# Wetter.net
KiCad netlist of a schematic drawn in EAGLE
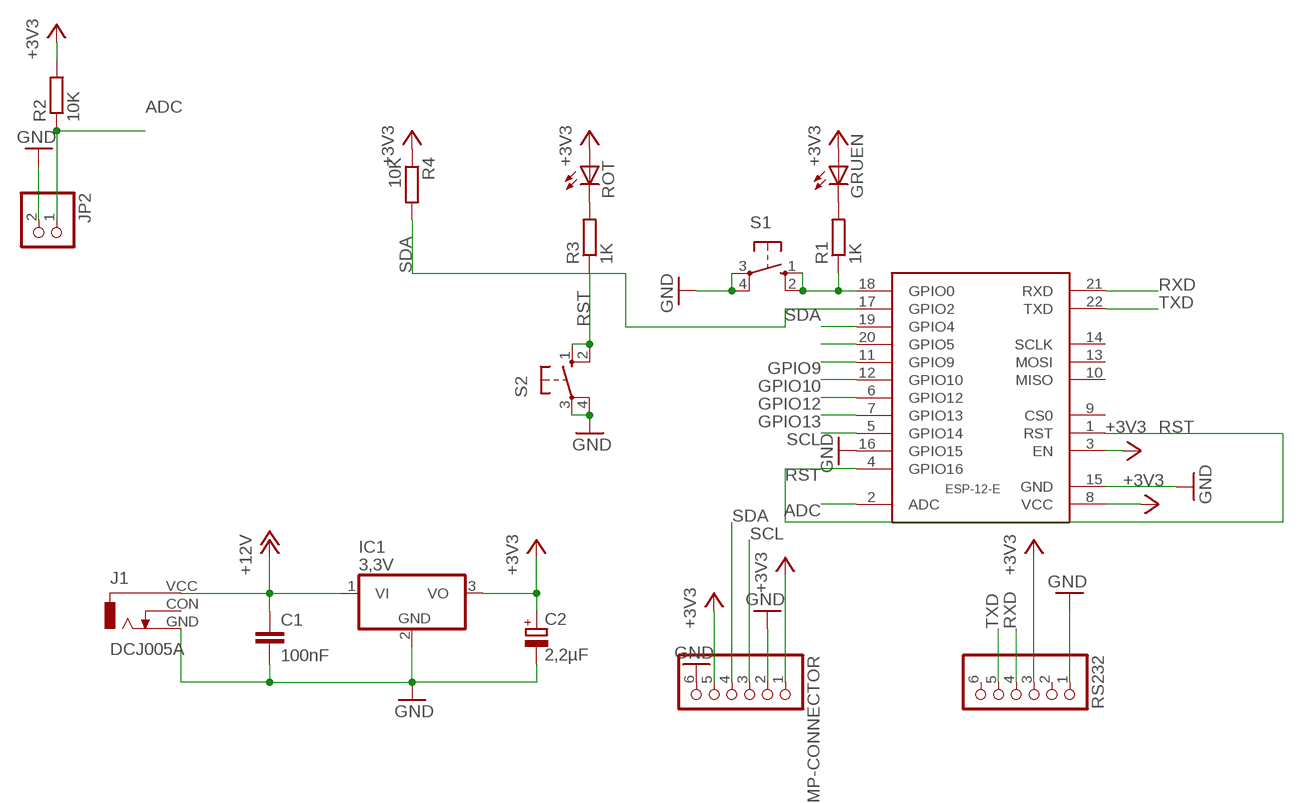
[diagram p0: schematic, sheet 1]

(export (version "E")
  (design (tool "Eeschema 10.0.6"))
  (components
    (comp (ref "BMP-CONNECTOR")
      (value "PINHD-1X6")
      (footprint "eagle-import:1X06")
      (libsource (lib "eagle-import") (part "PINHD-1X6"))
    )
    (comp (ref "C1")
      (value "100nF")
      (footprint "eagle-import:C050-030X075")
      (libsource (lib "eagle-import") (part "C-EU050-030X075"))
    )
    (comp (ref "C2")
      (value "2,2µF")
      (footprint "eagle-import:E2,5-6")
      (libsource (lib "eagle-import") (part "CPOL-EUE2.5-6"))
    )
    (comp (ref "GRUEN")
      (value "LED5MM")
      (footprint "eagle-import:LED5MM")
      (libsource (lib "eagle-import") (part "LED5MM"))
    )
    (comp (ref "IC1")
      (value "3,3V")
      (footprint "eagle-import:TO220V")
      (libsource (lib "eagle-import") (part "78TV05"))
    )
    (comp (ref "J1")
      (value "DCJ005A")
      (footprint "eagle-import:DC005A")
      (libsource (lib "eagle-import") (part "DCJ005A"))
    )
    (comp (ref "JP2")
      (value "PINHD-1X2")
      (footprint "eagle-import:1X02")
      (libsource (lib "eagle-import") (part "PINHD-1X2"))
    )
    (comp (ref "R1")
      (value "1K")
      (footprint "eagle-import:0207_10")
      (libsource (lib "eagle-import") (part "R-EU_0207/10"))
    )
    (comp (ref "R2")
      (value "10K")
      (footprint "eagle-import:0207_10")
      (libsource (lib "eagle-import") (part "R-EU_0207/10"))
    )
    (comp (ref "R3")
      (value "1K")
      (footprint "eagle-import:0207_10")
      (libsource (lib "eagle-import") (part "R-EU_0207/10"))
    )
    (comp (ref "R4")
      (value "10K")
      (footprint "eagle-import:0207_10")
      (libsource (lib "eagle-import") (part "R-EU_0207/10"))
    )
    (comp (ref "ROT")
      (value "LED5MM")
      (footprint "eagle-import:LED5MM")
      (libsource (lib "eagle-import") (part "LED5MM"))
    )
    (comp (ref "RS232")
      (value "PINHD-1X6")
      (footprint "eagle-import:1X06")
      (libsource (lib "eagle-import") (part "pinhead_PINHD-1X6"))
    )
    (comp (ref "S1")
      (value "10-XX")
      (footprint "eagle-import:B3F-10XX")
      (fields (field (name "MPN") "B3F-1000"))
      (libsource (lib "eagle-import") (part "10-XX"))
    )
    (comp (ref "S2")
      (value "10-XX")
      (footprint "eagle-import:B3F-10XX")
      (fields (field (name "MPN") "B3F-1000"))
      (libsource (lib "eagle-import") (part "10-XX"))
    )
    (comp (ref "U$1")
      (value "ESP-12-E")
      (footprint "eagle-import:ESP-12-E")
      (libsource (lib "eagle-import") (part "ESP-12-E"))
    )
  )
  (nets
    (net (code "1") (name "+3V3") (class "Default")
      (node (ref "BMP-CONNECTOR") (pin "1") (pinfunction "1_1") (pintype "passive"))
      (node (ref "BMP-CONNECTOR") (pin "5") (pinfunction "5_5") (pintype "passive"))
      (node (ref "C2") (pin "+") (pinfunction "+_+") (pintype "passive"))
      (node (ref "GRUEN") (pin "A") (pinfunction "A_A") (pintype "passive"))
      (node (ref "IC1") (pin "3") (pinfunction "VO_3") (pintype "passive"))
      (node (ref "R2") (pin "2") (pinfunction "2_2") (pintype "passive"))
      (node (ref "R4") (pin "1") (pinfunction "1_1") (pintype "passive"))
      (node (ref "ROT") (pin "A") (pinfunction "A_A") (pintype "passive"))
      (node (ref "RS232") (pin "3") (pinfunction "3_3") (pintype "passive"))
      (node (ref "U$1") (pin "3") (pinfunction "EN_3") (pintype "bidirectional"))
      (node (ref "U$1") (pin "8") (pinfunction "VCC_8") (pintype "power_in"))
    )
    (net (code "2") (name "+12V") (class "Default")
      (node (ref "C1") (pin "1") (pinfunction "1_1") (pintype "passive"))
      (node (ref "IC1") (pin "1") (pinfunction "VI_1") (pintype "input"))
      (node (ref "J1") (pin "VCC") (pinfunction "1_VCC") (pintype "passive"))
    )
    (net (code "3") (name "/ADC") (class "Default")
      (node (ref "JP2") (pin "1") (pinfunction "1_1") (pintype "passive"))
      (node (ref "R2") (pin "1") (pinfunction "1_1") (pintype "passive"))
      (node (ref "U$1") (pin "2") (pinfunction "ADC_2") (pintype "bidirectional"))
    )
    (net (code "4") (name "/GPIO9") (class "Default")
      (node (ref "U$1") (pin "11") (pinfunction "GPIO9_11") (pintype "bidirectional"))
    )
    (net (code "5") (name "/GPIO10") (class "Default")
      (node (ref "U$1") (pin "12") (pinfunction "GPIO10_12") (pintype "bidirectional"))
    )
    (net (code "6") (name "/GPIO12") (class "Default")
      (node (ref "U$1") (pin "6") (pinfunction "GPIO12_6") (pintype "bidirectional"))
    )
    (net (code "7") (name "/GPIO13") (class "Default")
      (node (ref "U$1") (pin "7") (pinfunction "GPIO13_7") (pintype "bidirectional"))
    )
    (net (code "8") (name "/RST") (class "Default")
      (node (ref "R3") (pin "1") (pinfunction "1_1") (pintype "passive"))
      (node (ref "S2") (pin "1") (pinfunction "S_1") (pintype "passive"))
      (node (ref "S2") (pin "2") (pinfunction "S1_2") (pintype "passive"))
      (node (ref "U$1") (pin "1") (pinfunction "RST_1") (pintype "bidirectional"))
      (node (ref "U$1") (pin "4") (pinfunction "GPIO16_4") (pintype "bidirectional"))
    )
    (net (code "9") (name "/RXD") (class "Default")
      (node (ref "RS232") (pin "4") (pinfunction "4_4") (pintype "passive"))
      (node (ref "U$1") (pin "21") (pinfunction "RXD_21") (pintype "bidirectional"))
    )
    (net (code "10") (name "/SCL") (class "Default")
      (node (ref "BMP-CONNECTOR") (pin "3") (pinfunction "3_3") (pintype "passive"))
      (node (ref "U$1") (pin "5") (pinfunction "GPIO14_5") (pintype "bidirectional"))
    )
    (net (code "11") (name "/SDA") (class "Default")
      (node (ref "BMP-CONNECTOR") (pin "4") (pinfunction "4_4") (pintype "passive"))
      (node (ref "R4") (pin "2") (pinfunction "2_2") (pintype "passive"))
      (node (ref "U$1") (pin "17") (pinfunction "GPIO2_17") (pintype "bidirectional"))
    )
    (net (code "12") (name "/TXD") (class "Default")
      (node (ref "RS232") (pin "5") (pinfunction "5_5") (pintype "passive"))
      (node (ref "U$1") (pin "22") (pinfunction "TXD_22") (pintype "bidirectional"))
    )
    (net (code "13") (name "GND") (class "Default")
      (node (ref "BMP-CONNECTOR") (pin "2") (pinfunction "2_2") (pintype "passive"))
      (node (ref "BMP-CONNECTOR") (pin "6") (pinfunction "6_6") (pintype "passive"))
      (node (ref "C1") (pin "2") (pinfunction "2_2") (pintype "passive"))
      (node (ref "C2") (pin "-") (pinfunction "-_-") (pintype "passive"))
      (node (ref "IC1") (pin "2") (pinfunction "GND_2") (pintype "passive"))
      (node (ref "J1") (pin "GND") (pinfunction "3_GND") (pintype "passive"))
      (node (ref "JP2") (pin "2") (pinfunction "2_2") (pintype "passive"))
      (node (ref "RS232") (pin "1") (pinfunction "1_1") (pintype "passive"))
      (node (ref "S1") (pin "3") (pinfunction "P_3") (pintype "passive"))
      (node (ref "S1") (pin "4") (pinfunction "P1_4") (pintype "passive"))
      (node (ref "S2") (pin "3") (pinfunction "P_3") (pintype "passive"))
      (node (ref "S2") (pin "4") (pinfunction "P1_4") (pintype "passive"))
      (node (ref "U$1") (pin "15") (pinfunction "GND_15") (pintype "power_in"))
      (node (ref "U$1") (pin "16") (pinfunction "GPIO15_16") (pintype "bidirectional"))
    )
    (net (code "14") (name "Net-(GRUEN-C)") (class "Default")
      (node (ref "GRUEN") (pin "K") (pinfunction "C_K") (pintype "passive"))
      (node (ref "R1") (pin "2") (pinfunction "2_2") (pintype "passive"))
    )
    (net (code "15") (name "Net-(ROT-C)") (class "Default")
      (node (ref "R3") (pin "2") (pinfunction "2_2") (pintype "passive"))
      (node (ref "ROT") (pin "K") (pinfunction "C_K") (pintype "passive"))
    )
    (net (code "16") (name "Net-(S1-S)") (class "Default")
      (node (ref "R1") (pin "1") (pinfunction "1_1") (pintype "passive"))
      (node (ref "S1") (pin "1") (pinfunction "S_1") (pintype "passive"))
      (node (ref "S1") (pin "2") (pinfunction "S1_2") (pintype "passive"))
      (node (ref "U$1") (pin "18") (pinfunction "GPIO0_18") (pintype "bidirectional"))
    )
    (net (code "17") (name "unconnected-(J1-2-PadCON)") (class "Default")
      (node (ref "J1") (pin "CON") (pinfunction "2_CON") (pintype "passive"))
    )
    (net (code "18") (name "unconnected-(RS232-Pad2)") (class "Default")
      (node (ref "RS232") (pin "2") (pinfunction "2_2") (pintype "passive"))
    )
    (net (code "19") (name "unconnected-(RS232-Pad6)") (class "Default")
      (node (ref "RS232") (pin "6") (pinfunction "6_6") (pintype "passive"))
    )
    (net (code "20") (name "unconnected-(U$1-CS0-Pad9)") (class "Default")
      (node (ref "U$1") (pin "9") (pinfunction "CS0_9") (pintype "bidirectional"))
    )
    (net (code "21") (name "unconnected-(U$1-GPIO4-Pad19)") (class "Default")
      (node (ref "U$1") (pin "19") (pinfunction "GPIO4_19") (pintype "bidirectional"))
    )
    (net (code "22") (name "unconnected-(U$1-GPIO5-Pad20)") (class "Default")
      (node (ref "U$1") (pin "20") (pinfunction "GPIO5_20") (pintype "bidirectional"))
    )
    (net (code "23") (name "unconnected-(U$1-MISO-Pad10)") (class "Default")
      (node (ref "U$1") (pin "10") (pinfunction "MISO_10") (pintype "bidirectional"))
    )
    (net (code "24") (name "unconnected-(U$1-MOSI-Pad13)") (class "Default")
      (node (ref "U$1") (pin "13") (pinfunction "MOSI_13") (pintype "bidirectional"))
    )
    (net (code "25") (name "unconnected-(U$1-SCLK-Pad14)") (class "Default")
      (node (ref "U$1") (pin "14") (pinfunction "SCLK_14") (pintype "bidirectional"))
    )
  )
)
